# SCH_sonnn_2025-09-09.net
KiCad netlist of a schematic drawn in EasyEDA
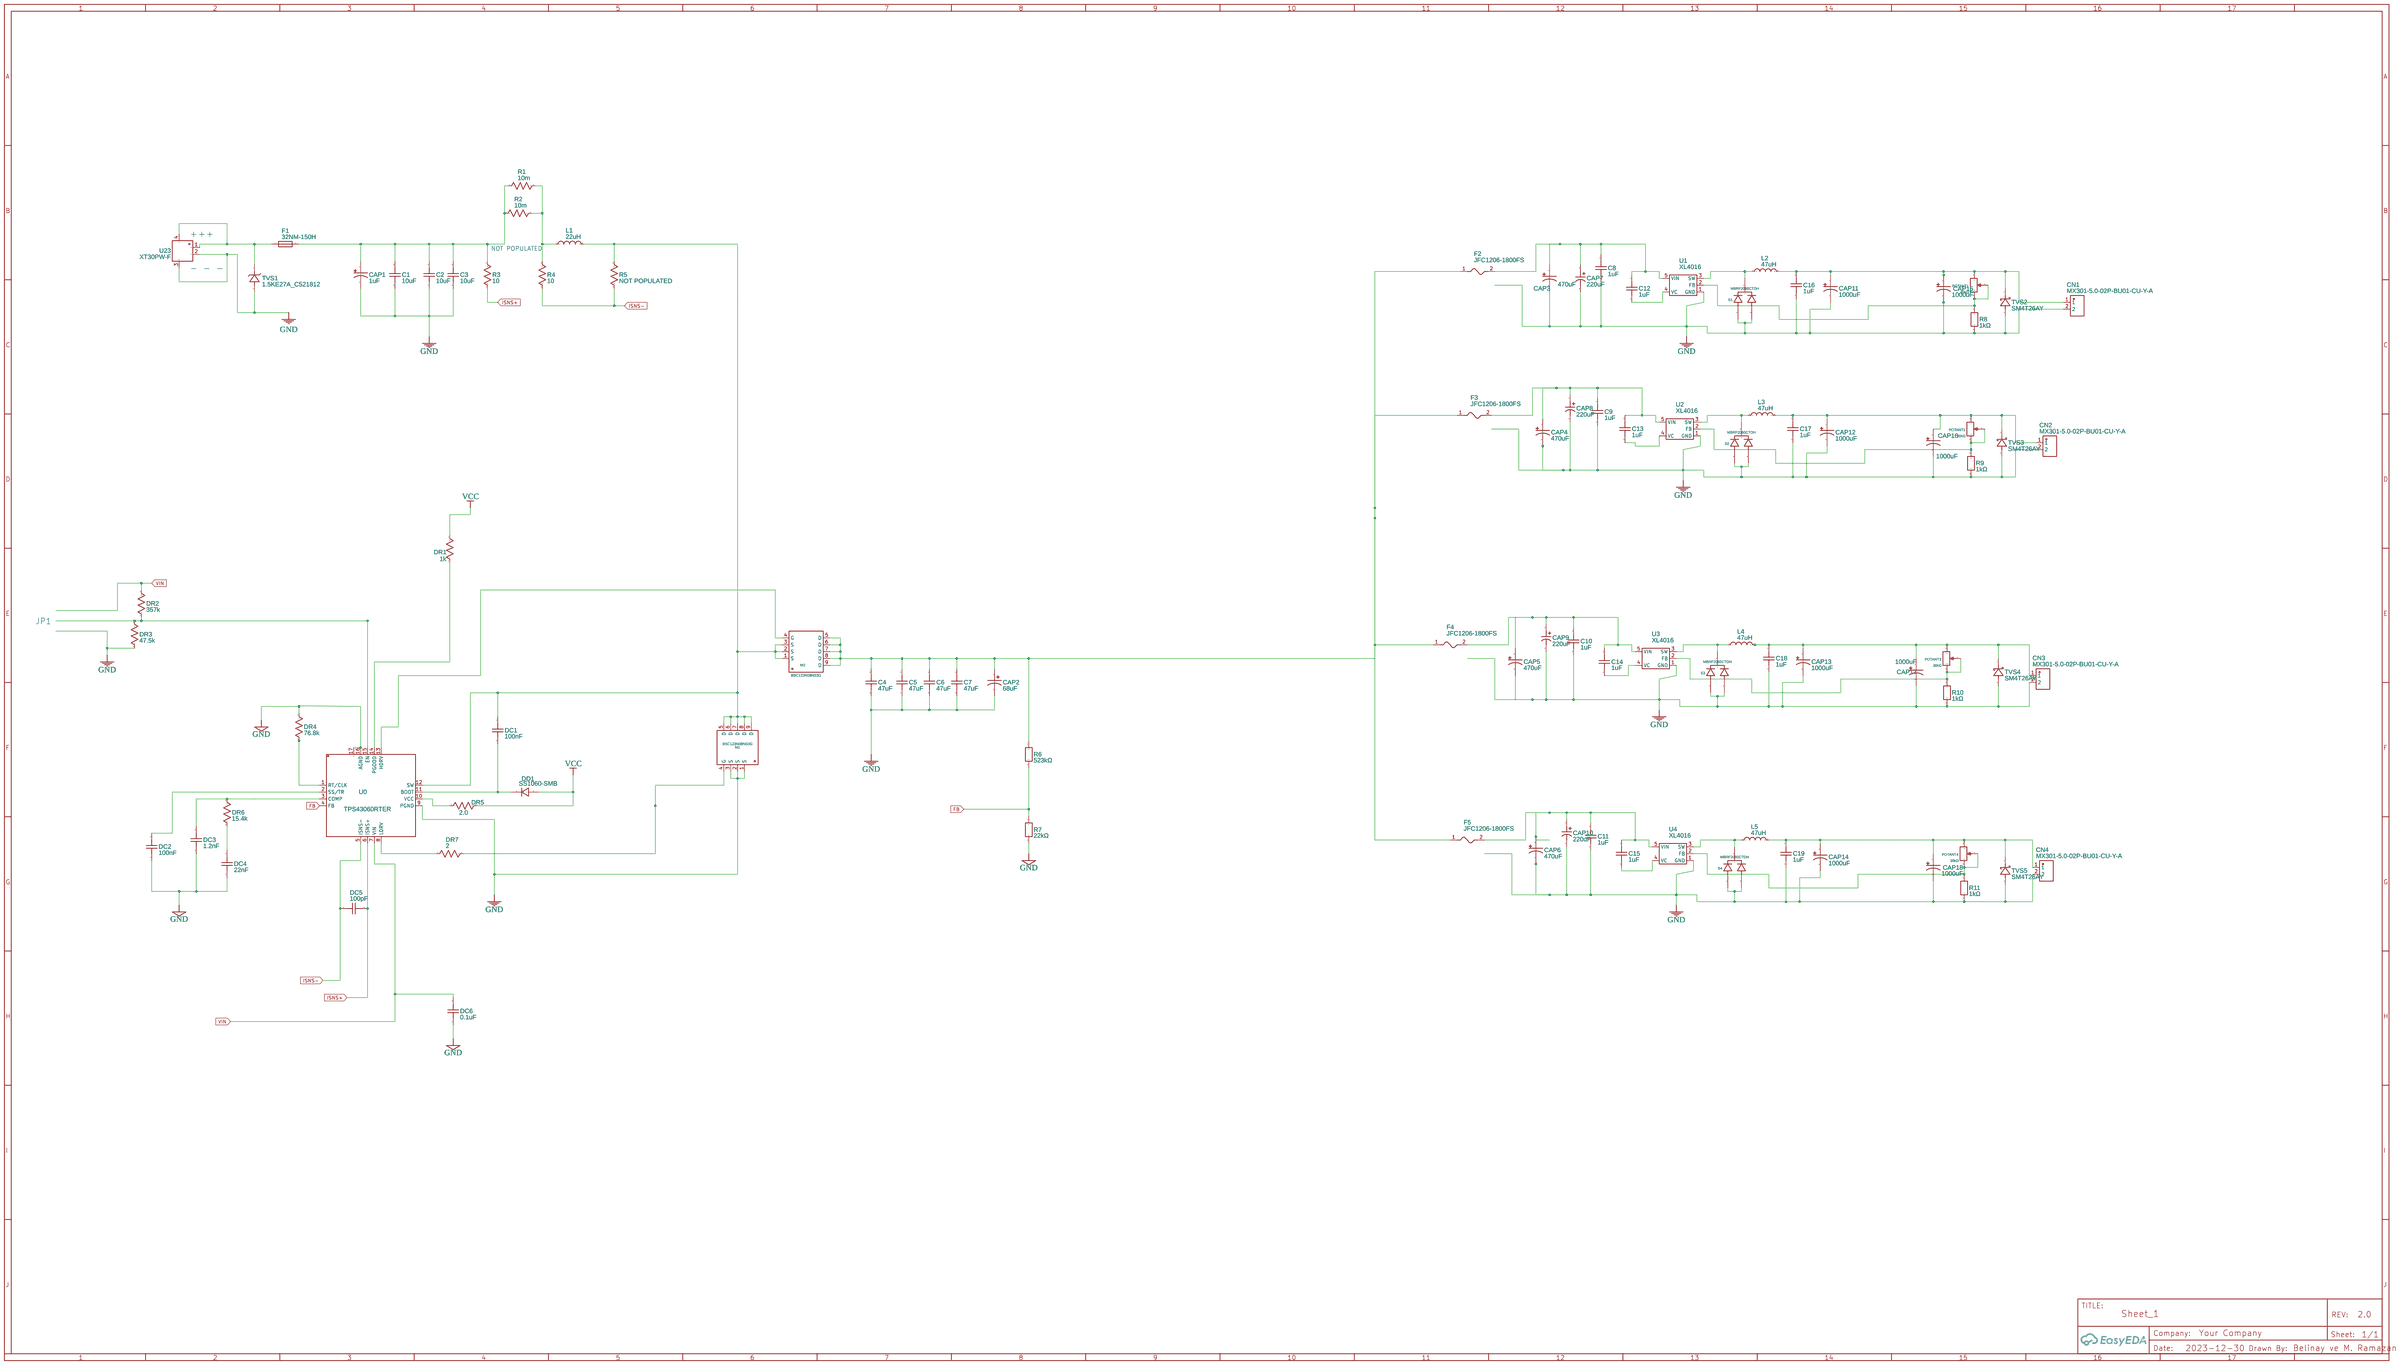
[diagram p0: schematic sheet]

(export (version "E")
  (design (tool "Eeschema 10.0.6"))
  (components
    (comp (ref "C1")
      (value "10uF")
      (fields (field (name "Manufacturer Part") "CNC6P1X7R1H106K250AE") (field (name "Manufacturer") "TDK"))
      (libsource (lib "") (part "CNC6P1X7R1H106K250AE"))
    )
    (comp (ref "C2")
      (value "10uF")
      (fields (field (name "Manufacturer Part") "CNC6P1X7R1H106K250AE") (field (name "Manufacturer") "TDK"))
      (libsource (lib "") (part "CNC6P1X7R1H106K250AE"))
    )
    (comp (ref "C3")
      (value "10uF")
      (fields (field (name "Manufacturer Part") "CNC6P1X7R1H106K250AE") (field (name "Manufacturer") "TDK"))
      (libsource (lib "") (part "CNC6P1X7R1H106K250AE"))
    )
    (comp (ref "C4") (value "47uF") (libsource (lib "") (part "C_0603_US")))
    (comp (ref "C5") (value "47uF") (libsource (lib "") (part "C_0603_US")))
    (comp (ref "C6") (value "47uF") (libsource (lib "") (part "C_0603_US")))
    (comp (ref "C7") (value "47uF") (libsource (lib "") (part "C_0603_US")))
    (comp (ref "C8")
      (value "1uF")
      (fields (field (name "Manufacturer Part") "FK26X7R1H105KRE06") (field (name "Manufacturer") "TDK"))
      (libsource (lib "") (part "FK26X7R1H105KRE06"))
    )
    (comp (ref "C9")
      (value "1uF")
      (fields (field (name "Manufacturer Part") "FK26X7R1H105KRE06") (field (name "Manufacturer") "TDK"))
      (libsource (lib "") (part "FK26X7R1H105KRE06"))
    )
    (comp (ref "C10")
      (value "1uF")
      (fields (field (name "Manufacturer Part") "FK26X7R1H105KRE06") (field (name "Manufacturer") "TDK"))
      (libsource (lib "") (part "FK26X7R1H105KRE06"))
    )
    (comp (ref "C11")
      (value "1uF")
      (fields (field (name "Manufacturer Part") "FK26X7R1H105KRE06") (field (name "Manufacturer") "TDK"))
      (libsource (lib "") (part "FK26X7R1H105KRE06"))
    )
    (comp (ref "C12")
      (value "1uF")
      (fields (field (name "Manufacturer Part") "C1005X6S1A105K050BC") (field (name "Manufacturer") "TDK"))
      (libsource (lib "") (part "C1005X6S1A105K050BC"))
    )
    (comp (ref "C13")
      (value "1uF")
      (fields (field (name "Manufacturer Part") "C1005X6S1A105K050BC") (field (name "Manufacturer") "TDK"))
      (libsource (lib "") (part "C1005X6S1A105K050BC"))
    )
    (comp (ref "C14")
      (value "1uF")
      (fields (field (name "Manufacturer Part") "C1005X6S1A105K050BC") (field (name "Manufacturer") "TDK"))
      (libsource (lib "") (part "C1005X6S1A105K050BC"))
    )
    (comp (ref "C15")
      (value "1uF")
      (fields (field (name "Manufacturer Part") "C1005X6S1A105K050BC") (field (name "Manufacturer") "TDK"))
      (libsource (lib "") (part "C1005X6S1A105K050BC_1"))
    )
    (comp (ref "C16")
      (value "1uF")
      (fields (field (name "Manufacturer Part") "FK26X7R1H105KRE06") (field (name "Manufacturer") "TDK"))
      (libsource (lib "") (part "FK26X7R1H105KRE06"))
    )
    (comp (ref "C17")
      (value "1uF")
      (fields (field (name "Manufacturer Part") "FK26X7R1H105KRE06") (field (name "Manufacturer") "TDK"))
      (libsource (lib "") (part "FK26X7R1H105KRE06_1"))
    )
    (comp (ref "C18")
      (value "1uF")
      (fields (field (name "Manufacturer Part") "FK26X7R1H105KRE06") (field (name "Manufacturer") "TDK"))
      (libsource (lib "") (part "FK26X7R1H105KRE06"))
    )
    (comp (ref "C19")
      (value "1uF")
      (fields (field (name "Manufacturer Part") "FK26X7R1H105KRE06") (field (name "Manufacturer") "TDK"))
      (libsource (lib "") (part "FK26X7R1H105KRE06"))
    )
    (comp (ref "CAP1")
      (value "1uF")
      (fields (field (name "Manufacturer Part") "HT2A1R0M0405") (field (name "Manufacturer") "HONOR(荣誉)"))
      (libsource (lib "") (part "RVT2A1R0M0405"))
    )
    (comp (ref "CAP2") (value "68uF") (libsource (lib "") (part "C_Tan_SMD_A_US")))
    (comp (ref "CAP3")
      (value "470uF")
      (fields
        (field (name "Manufacturer Part") "RC063M471LO13*20TH-2A1E")
        (field (name "Manufacturer") "BERYL(绿宝石)")
      )
      (libsource (lib "") (part "RC063M471LO13*20TH-2A1E_1"))
    )
    (comp (ref "CAP4")
      (value "470uF")
      (fields
        (field (name "Manufacturer Part") "RC063M471LO13*20TH-2A1E")
        (field (name "Manufacturer") "BERYL(绿宝石)")
      )
      (libsource (lib "") (part "RC063M471LO13*20TH-2A1E_1"))
    )
    (comp (ref "CAP5")
      (value "470uF")
      (fields
        (field (name "Manufacturer Part") "RC063M471LO13*20TH-2A1E")
        (field (name "Manufacturer") "BERYL(绿宝石)")
      )
      (libsource (lib "") (part "RC063M471LO13*20TH-2A1E_1"))
    )
    (comp (ref "CAP6")
      (value "470uF")
      (fields
        (field (name "Manufacturer Part") "RC063M471LO13*20TH-2A1E")
        (field (name "Manufacturer") "BERYL(绿宝石)")
      )
      (libsource (lib "") (part "RC063M471LO13*20TH-2A1E"))
    )
    (comp (ref "CAP7")
      (value "220uF")
      (fields (field (name "Manufacturer Part") "189RV0038") (field (name "Manufacturer") "KNSCHA(科尼盛)"))
      (libsource (lib "") (part "189RV0038"))
    )
    (comp (ref "CAP8")
      (value "220uF")
      (fields (field (name "Manufacturer Part") "189RV0038") (field (name "Manufacturer") "KNSCHA(科尼盛)"))
      (libsource (lib "") (part "189RV0038"))
    )
    (comp (ref "CAP9")
      (value "220uF")
      (fields (field (name "Manufacturer Part") "189RV0038") (field (name "Manufacturer") "KNSCHA(科尼盛)"))
      (libsource (lib "") (part "189RV0038"))
    )
    (comp (ref "CAP10")
      (value "220uF")
      (fields (field (name "Manufacturer Part") "189RV0038") (field (name "Manufacturer") "KNSCHA(科尼盛)"))
      (libsource (lib "") (part "189RV0038"))
    )
    (comp (ref "CAP11")
      (value "1000uF")
      (fields (field (name "Manufacturer Part") "PKCL2001H102MF") (field (name "Manufacturer") "Ymin(永铭)"))
      (libsource (lib "") (part "PKCL21H102MF"))
    )
    (comp (ref "CAP12")
      (value "1000uF")
      (fields (field (name "Manufacturer Part") "PKCL2001H102MF") (field (name "Manufacturer") "Ymin(永铭)"))
      (libsource (lib "") (part "PKCL21H102MF"))
    )
    (comp (ref "CAP13")
      (value "1000uF")
      (fields (field (name "Manufacturer Part") "PKCL2001H102MF") (field (name "Manufacturer") "Ymin(永铭)"))
      (libsource (lib "") (part "PKCL21H102MF"))
    )
    (comp (ref "CAP14")
      (value "1000uF")
      (fields (field (name "Manufacturer Part") "PKCL2001H102MF") (field (name "Manufacturer") "Ymin(永铭)"))
      (libsource (lib "") (part "PKCL21H102MF_1"))
    )
    (comp (ref "CAP15")
      (value "1000uF")
      (fields (field (name "Manufacturer Part") "LKML3001J102MF") (field (name "Manufacturer") "Ymin(永铭)"))
      (libsource (lib "") (part "LKML3001J102MF_1"))
    )
    (comp (ref "CAP16")
      (value "1000uF")
      (fields (field (name "Manufacturer Part") "LKML3001J102MF") (field (name "Manufacturer") "Ymin(永铭)"))
      (libsource (lib "") (part "LKML3001J102MF_1"))
    )
    (comp (ref "CAP17")
      (value "1000uF")
      (fields (field (name "Manufacturer Part") "LKML3001J102MF") (field (name "Manufacturer") "Ymin(永铭)"))
      (libsource (lib "") (part "LKML3001J102MF"))
    )
    (comp (ref "CAP18")
      (value "1000uF")
      (fields (field (name "Manufacturer Part") "LKML3001J102MF") (field (name "Manufacturer") "Ymin(永铭)"))
      (libsource (lib "") (part "LKML3001J102MF"))
    )
    (comp (ref "CN1")
      (value "MX301-5.0-02P-BU01-CU-Y-A")
      (fields
        (field (name "Manufacturer Part") "MX301-5.0-02P-BU01-Cu-Y-A")
        (field (name "Manufacturer") "MAX(迈旭)")
      )
      (libsource (lib "") (part "MX301-5.0-02P-BU01-CU-Y-A"))
    )
    (comp (ref "CN2")
      (value "MX301-5.0-02P-BU01-CU-Y-A")
      (fields
        (field (name "Manufacturer Part") "MX301-5.0-02P-BU01-Cu-Y-A")
        (field (name "Manufacturer") "MAX(迈旭)")
      )
      (libsource (lib "") (part "MX301-5.0-02P-BU01-CU-Y-A"))
    )
    (comp (ref "CN3")
      (value "MX301-5.0-02P-BU01-CU-Y-A")
      (fields
        (field (name "Manufacturer Part") "MX301-5.0-02P-BU01-Cu-Y-A")
        (field (name "Manufacturer") "MAX(迈旭)")
      )
      (libsource (lib "") (part "MX301-5.0-02P-BU01-CU-Y-A"))
    )
    (comp (ref "CN4")
      (value "MX301-5.0-02P-BU01-CU-Y-A")
      (fields
        (field (name "Manufacturer Part") "MX301-5.0-02P-BU01-Cu-Y-A")
        (field (name "Manufacturer") "MAX(迈旭)")
      )
      (libsource (lib "") (part "MX301-5.0-02P-BU01-CU-Y-A"))
    )
    (comp (ref "DC1")
      (value "100nF")
      (fields
        (field (name "Manufacturer Part") "DCS104M26Y5UH6FJ5A0")
        (field (name "Manufacturer") "SHM(南方宏明)")
      )
      (libsource (lib "") (part "DCS104M26Y5UH6FJ5A0"))
    )
    (comp (ref "DC2")
      (value "100nF")
      (fields
        (field (name "Manufacturer Part") "DCS104M26Y5UH6FJ5A0")
        (field (name "Manufacturer") "SHM(南方宏明)")
      )
      (libsource (lib "") (part "DCS104M26Y5UH6FJ5A0_1"))
    )
    (comp (ref "DC3")
      (value "1.2nF")
      (fields (field (name "Manufacturer Part") "PE122J2A0501") (field (name "Manufacturer") "KYET(科雅)"))
      (libsource (lib "") (part "PE122J2A0501"))
    )
    (comp (ref "DC4")
      (value "22nF")
      (fields
        (field (name "Manufacturer Part") "DCM223M39Y5VL6FJ5A0")
        (field (name "Manufacturer") "SHM(南方宏明)")
      )
      (libsource (lib "") (part "DCM223M39Y5VL6FJ5A0"))
    )
    (comp (ref "DC5")
      (value "100pF")
      (fields
        (field (name "Manufacturer Part") "DCC101J26COHF6FJ5A0")
        (field (name "Manufacturer") "SHM(南方宏明)")
      )
      (libsource (lib "") (part "DCC101J26COHF6FJ5A0"))
    )
    (comp (ref "DC6") (value "0.1uF") (libsource (lib "") (part "C_0603_US_1")))
    (comp (ref "DD1")
      (value "SS1060-SMB")
      (fields (field (name "Manufacturer") "GOODWORK(固得沃克)"))
      (libsource (lib "") (part "SS1060-SMB"))
    )
    (comp (ref "DR1") (value "1k") (libsource (lib "") (part "R_AXIAL-0.3_US_1")))
    (comp (ref "DR2") (value "357k") (libsource (lib "") (part "R_AXIAL-0.3_US_1")))
    (comp (ref "DR3") (value "47.5k") (libsource (lib "") (part "R_AXIAL-0.3_US_1")))
    (comp (ref "DR4") (value "76.8k") (libsource (lib "") (part "R_AXIAL-0.3_US_1")))
    (comp (ref "DR5") (value "2.0") (libsource (lib "") (part "R_AXIAL-0.3_US")))
    (comp (ref "DR6") (value "15.4k") (libsource (lib "") (part "R_AXIAL-0.3_US_1")))
    (comp (ref "DR7") (value "2") (libsource (lib "") (part "R_0603_US")))
    (comp (ref "F1")
      (value "32NM-150H")
      (fields (field (name "Manufacturer") "HOLLY(好利来)"))
      (libsource (lib "") (part "32NM-150H"))
    )
    (comp (ref "F2")
      (value "JFC1206-1800FS")
      (fields (field (name "Manufacturer") "JDTfuse(集电通)"))
      (libsource (lib "") (part "JFC1206-1800FS"))
    )
    (comp (ref "F3")
      (value "JFC1206-1800FS")
      (fields (field (name "Manufacturer") "JDTfuse(集电通)"))
      (libsource (lib "") (part "JFC1206-1800FS"))
    )
    (comp (ref "F4")
      (value "JFC1206-1800FS")
      (fields (field (name "Manufacturer") "JDTfuse(集电通)"))
      (libsource (lib "") (part "JFC1206-1800FS"))
    )
    (comp (ref "F5")
      (value "JFC1206-1800FS")
      (fields (field (name "Manufacturer") "JDTfuse(集电通)"))
      (libsource (lib "") (part "JFC1206-1800FS"))
    )
    (comp (ref "L1")
      (value "22uH")
      (fields
        (field (name "Manufacturer Part") "PDMTAT068125-220MLU")
        (field (name "Manufacturer") "PROD(谱罗德)")
      )
      (libsource (lib "") (part "PDMTAT068125-220MLU"))
    )
    (comp (ref "L2")
      (value "47uH")
      (fields (field (name "Manufacturer Part") "PDPMAA1712-470MP") (field (name "Manufacturer") "PROD(谱罗德)"))
      (libsource (lib "") (part "PDPMAA1712-470MP"))
    )
    (comp (ref "L3")
      (value "47uH")
      (fields (field (name "Manufacturer Part") "PDPMAA1712-470MP") (field (name "Manufacturer") "PROD(谱罗德)"))
      (libsource (lib "") (part "PDPMAA1712-470MP"))
    )
    (comp (ref "L4")
      (value "47uH")
      (fields (field (name "Manufacturer Part") "PDPMAA1712-470MP") (field (name "Manufacturer") "PROD(谱罗德)"))
      (libsource (lib "") (part "PDPMAA1712-470MP"))
    )
    (comp (ref "L5")
      (value "47uH")
      (fields (field (name "Manufacturer Part") "PDPMAA1712-470MP") (field (name "Manufacturer") "PROD(谱罗德)"))
      (libsource (lib "") (part "PDPMAA1712-470MP"))
    )
    (comp (ref "M1")
      (value "BSC123N08NS3G")
      (fields (field (name "Manufacturer") "Infineon(英飞凌)"))
      (libsource (lib "") (part "BSC123N08NS3G_1"))
    )
    (comp (ref "M2")
      (value "BSC123N08NS3G")
      (fields (field (name "Manufacturer") "Infineon(英飞凌)"))
      (libsource (lib "") (part "BSC123N08NS3G"))
    )
    (comp (ref "POTANT1")
      (value "30kΩ")
      (fields (field (name "Manufacturer Part") "3362P-1-103LF") (field (name "Manufacturer") "BOURNS"))
      (libsource (lib "") (part "3362P-1-103LF"))
    )
    (comp (ref "POTANT2")
      (value "30kΩ")
      (fields (field (name "Manufacturer Part") "3362P-1-103LF") (field (name "Manufacturer") "BOURNS"))
      (libsource (lib "") (part "3362P-1-103LF"))
    )
    (comp (ref "POTANT3")
      (value "30kΩ")
      (fields (field (name "Manufacturer Part") "3362P-1-103LF") (field (name "Manufacturer") "BOURNS"))
      (libsource (lib "") (part "3362P-1-103LF"))
    )
    (comp (ref "POTANT4")
      (value "30kΩ")
      (fields (field (name "Manufacturer Part") "3362P-1-103LF") (field (name "Manufacturer") "BOURNS"))
      (libsource (lib "") (part "3362P-1-103LF"))
    )
    (comp (ref "R1") (value "10m") (libsource (lib "") (part "R_AXIAL-0.3_US_2")))
    (comp (ref "R2") (value "10m") (libsource (lib "") (part "R_AXIAL-0.3_US_2")))
    (comp (ref "R3") (value "10") (libsource (lib "") (part "R_AXIAL-0.3_US_3")))
    (comp (ref "R4") (value "10") (libsource (lib "") (part "R_AXIAL-0.3_US_3")))
    (comp (ref "R5") (value "NOT POPULATED") (libsource (lib "") (part "R_AXIAL-0.3_US_3")))
    (comp (ref "R6")
      (value "523kΩ")
      (fields (field (name "Manufacturer Part") "MFR-25FBF52-523K") (field (name "Manufacturer") "YAGEO(国巨)"))
      (libsource (lib "") (part "MFR-25FBF52-523K"))
    )
    (comp (ref "R7")
      (value "22kΩ")
      (fields
        (field (name "Manufacturer Part") "RN 3WS 22K F T/B A1")
        (field (name "Manufacturer") "Tyohm(幸亚电阻)")
      )
      (libsource (lib "") (part "RN 3WS 22K F T/B A1"))
    )
    (comp (ref "R8")
      (value "1kΩ")
      (fields (field (name "Manufacturer Part") "MF0207FTE52-1K") (field (name "Manufacturer") "YAGEO(国巨)"))
      (libsource (lib "") (part "MF0207FTE52-1K"))
    )
    (comp (ref "R9")
      (value "1kΩ")
      (fields (field (name "Manufacturer Part") "MF0207FTE52-1K") (field (name "Manufacturer") "YAGEO(国巨)"))
      (libsource (lib "") (part "MF0207FTE52-1K"))
    )
    (comp (ref "R10")
      (value "1kΩ")
      (fields (field (name "Manufacturer Part") "MF0207FTE52-1K") (field (name "Manufacturer") "YAGEO(国巨)"))
      (libsource (lib "") (part "MF0207FTE52-1K"))
    )
    (comp (ref "R11")
      (value "1kΩ")
      (fields (field (name "Manufacturer Part") "MF0207FTE52-1K") (field (name "Manufacturer") "YAGEO(国巨)"))
      (libsource (lib "") (part "MF0207FTE52-1K"))
    )
    (comp (ref "S1")
      (value "MBRF2060CTDH")
      (fields (field (name "Manufacturer") "迪一"))
      (libsource (lib "") (part "MBRF2060CTDH"))
    )
    (comp (ref "S2")
      (value "MBRF2060CTDH")
      (fields (field (name "Manufacturer") "迪一"))
      (libsource (lib "") (part "MBRF2060CTDH"))
    )
    (comp (ref "S3")
      (value "MBRF2060CTDH")
      (fields (field (name "Manufacturer") "迪一"))
      (libsource (lib "") (part "MBRF2060CTDH"))
    )
    (comp (ref "S4")
      (value "MBRF2060CTDH")
      (fields (field (name "Manufacturer") "迪一"))
      (libsource (lib "") (part "MBRF2060CTDH"))
    )
    (comp (ref "TVS1")
      (value "1.5KE27A_C521812")
      (fields
        (field (name "Manufacturer Part") "1.5KE27A/B")
        (field (name "Manufacturer") "Brightking(君耀电子)")
      )
      (libsource (lib "") (part "1.5KE27A_C521812"))
    )
    (comp (ref "TVS2")
      (value "SM4T26AY")
      (fields (field (name "Manufacturer") "ST(意法半导体)"))
      (libsource (lib "") (part "SM4T26AY"))
    )
    (comp (ref "TVS3")
      (value "SM4T26AY")
      (fields (field (name "Manufacturer") "ST(意法半导体)"))
      (libsource (lib "") (part "SM4T26AY"))
    )
    (comp (ref "TVS4")
      (value "SM4T26AY")
      (fields (field (name "Manufacturer") "ST(意法半导体)"))
      (libsource (lib "") (part "SM4T26AY"))
    )
    (comp (ref "TVS5")
      (value "SM4T26AY")
      (fields (field (name "Manufacturer") "ST(意法半导体)"))
      (libsource (lib "") (part "SM4T26AY"))
    )
    (comp (ref "U0")
      (value "TPS43060RTER")
      (fields (field (name "Manufacturer") "TI(德州仪器)"))
      (libsource (lib "") (part "TPS43060RTER"))
    )
    (comp (ref "U1")
      (value "XL4016")
      (fields (field (name "Manufacturer Part") "XL4016E1") (field (name "Manufacturer") "XLSEMI"))
      (libsource (lib "") (part "XL4016"))
    )
    (comp (ref "U2")
      (value "XL4016")
      (fields (field (name "Manufacturer Part") "XL4016E1") (field (name "Manufacturer") "XLSEMI"))
      (libsource (lib "") (part "XL4016"))
    )
    (comp (ref "U3")
      (value "XL4016")
      (fields (field (name "Manufacturer Part") "XL4016E1") (field (name "Manufacturer") "XLSEMI"))
      (libsource (lib "") (part "XL4016"))
    )
    (comp (ref "U4")
      (value "XL4016")
      (fields (field (name "Manufacturer Part") "XL4016E1") (field (name "Manufacturer") "XLSEMI"))
      (libsource (lib "") (part "XL4016"))
    )
    (comp (ref "U23") (value "XT30PW-F") (libsource (lib "") (part "XT30PW-F")))
  )
  (nets
    (net (code "1") (name "FB") (class "Default")
      (node (ref "R6") (pin "1") (pinfunction "1_1") (pintype "unspecified"))
      (node (ref "R7") (pin "1") (pinfunction "1_1") (pintype "unspecified"))
      (node (ref "U0") (pin "4") (pinfunction "FB_4") (pintype "unspecified"))
    )
    (net (code "2") (name "GND") (class "Default")
      (node (ref "C1") (pin "1") (pinfunction "1_1") (pintype "unspecified"))
      (node (ref "C10") (pin "2") (pinfunction "2_2") (pintype "unspecified"))
      (node (ref "C11") (pin "2") (pinfunction "2_2") (pintype "unspecified"))
      (node (ref "C16") (pin "2") (pinfunction "2_2") (pintype "unspecified"))
      (node (ref "C17") (pin "1") (pinfunction "1_1") (pintype "unspecified"))
      (node (ref "C18") (pin "2") (pinfunction "2_2") (pintype "unspecified"))
      (node (ref "C19") (pin "2") (pinfunction "2_2") (pintype "unspecified"))
      (node (ref "C2") (pin "1") (pinfunction "1_1") (pintype "unspecified"))
      (node (ref "C3") (pin "1") (pinfunction "1_1") (pintype "unspecified"))
      (node (ref "C4") (pin "1") (pinfunction "1_1") (pintype "unspecified"))
      (node (ref "C5") (pin "1") (pinfunction "1_1") (pintype "unspecified"))
      (node (ref "C6") (pin "1") (pinfunction "1_1") (pintype "unspecified"))
      (node (ref "C7") (pin "1") (pinfunction "1_1") (pintype "unspecified"))
      (node (ref "C8") (pin "2") (pinfunction "2_2") (pintype "unspecified"))
      (node (ref "C9") (pin "2") (pinfunction "2_2") (pintype "unspecified"))
      (node (ref "CAP1") (pin "2") (pinfunction "2_2") (pintype "unspecified"))
      (node (ref "CAP10") (pin "2") (pinfunction "2_2") (pintype "input"))
      (node (ref "CAP11") (pin "2") (pinfunction "2_2") (pintype "unspecified"))
      (node (ref "CAP12") (pin "2") (pinfunction "2_2") (pintype "unspecified"))
      (node (ref "CAP13") (pin "2") (pinfunction "2_2") (pintype "unspecified"))
      (node (ref "CAP14") (pin "2") (pinfunction "2_2") (pintype "unspecified"))
      (node (ref "CAP15") (pin "2") (pinfunction "2_2") (pintype "unspecified"))
      (node (ref "CAP16") (pin "2") (pinfunction "2_2") (pintype "unspecified"))
      (node (ref "CAP17") (pin "2") (pinfunction "2_2") (pintype "unspecified"))
      (node (ref "CAP18") (pin "2") (pinfunction "2_2") (pintype "unspecified"))
      (node (ref "CAP2") (pin "2") (pinfunction "2_2") (pintype "unspecified"))
      (node (ref "CAP3") (pin "2") (pinfunction "2_2") (pintype "unspecified"))
      (node (ref "CAP4") (pin "2") (pinfunction "2_2") (pintype "unspecified"))
      (node (ref "CAP5") (pin "2") (pinfunction "2_2") (pintype "unspecified"))
      (node (ref "CAP6") (pin "2") (pinfunction "2_2") (pintype "unspecified"))
      (node (ref "CAP7") (pin "2") (pinfunction "2_2") (pintype "input"))
      (node (ref "CAP8") (pin "2") (pinfunction "2_2") (pintype "input"))
      (node (ref "CAP9") (pin "2") (pinfunction "2_2") (pintype "input"))
      (node (ref "CN1") (pin "2") (pinfunction "2_2") (pintype "unspecified"))
      (node (ref "CN2") (pin "2") (pinfunction "2_2") (pintype "unspecified"))
      (node (ref "CN3") (pin "2") (pinfunction "2_2") (pintype "unspecified"))
      (node (ref "CN4") (pin "2") (pinfunction "2_2") (pintype "unspecified"))
      (node (ref "DC2") (pin "1") (pinfunction "1_1") (pintype "unspecified"))
      (node (ref "DC3") (pin "1") (pinfunction "1_1") (pintype "unspecified"))
      (node (ref "DC4") (pin "1") (pinfunction "1_1") (pintype "unspecified"))
      (node (ref "DC6") (pin "1") (pinfunction "1_1") (pintype "unspecified"))
      (node (ref "DR3") (pin "1") (pinfunction "1_1") (pintype "unspecified"))
      (node (ref "DR4") (pin "2") (pinfunction "2_2") (pintype "unspecified"))
      (node (ref "M1") (pin "1") (pinfunction "S_1") (pintype "unspecified"))
      (node (ref "M1") (pin "2") (pinfunction "S_2") (pintype "unspecified"))
      (node (ref "M1") (pin "3") (pinfunction "S_3") (pintype "unspecified"))
      (node (ref "R10") (pin "2") (pinfunction "2_2") (pintype "unspecified"))
      (node (ref "R11") (pin "2") (pinfunction "2_2") (pintype "unspecified"))
      (node (ref "R7") (pin "2") (pinfunction "2_2") (pintype "unspecified"))
      (node (ref "R8") (pin "2") (pinfunction "2_2") (pintype "unspecified"))
      (node (ref "R9") (pin "2") (pinfunction "2_2") (pintype "unspecified"))
      (node (ref "S1") (pin "1") (pinfunction "1_1") (pintype "unspecified"))
      (node (ref "S1") (pin "3") (pinfunction "3_3") (pintype "unspecified"))
      (node (ref "S2") (pin "1") (pinfunction "1_1") (pintype "unspecified"))
      (node (ref "S2") (pin "3") (pinfunction "3_3") (pintype "unspecified"))
      (node (ref "S3") (pin "1") (pinfunction "1_1") (pintype "unspecified"))
      (node (ref "S3") (pin "3") (pinfunction "3_3") (pintype "unspecified"))
      (node (ref "S4") (pin "1") (pinfunction "1_1") (pintype "unspecified"))
      (node (ref "S4") (pin "3") (pinfunction "3_3") (pintype "unspecified"))
      (node (ref "TVS1") (pin "2") (pinfunction "A_2") (pintype "unspecified"))
      (node (ref "TVS2") (pin "2") (pinfunction "2_2") (pintype "unspecified"))
      (node (ref "TVS3") (pin "2") (pinfunction "2_2") (pintype "unspecified"))
      (node (ref "TVS4") (pin "2") (pinfunction "2_2") (pintype "unspecified"))
      (node (ref "TVS5") (pin "2") (pinfunction "2_2") (pintype "unspecified"))
      (node (ref "U0") (pin "16") (pinfunction "AGND_16") (pintype "unspecified"))
      (node (ref "U0") (pin "17") (pinfunction "PAD_17") (pintype "unspecified"))
      (node (ref "U0") (pin "9") (pinfunction "PGND_9") (pintype "unspecified"))
      (node (ref "U1") (pin "1") (pinfunction "GND_1") (pintype "unspecified"))
      (node (ref "U2") (pin "1") (pinfunction "GND_1") (pintype "unspecified"))
      (node (ref "U23") (pin "2") (pinfunction "2_2") (pintype "unspecified"))
      (node (ref "U23") (pin "3") (pinfunction "3_3") (pintype "unspecified"))
      (node (ref "U3") (pin "1") (pinfunction "GND_1") (pintype "unspecified"))
      (node (ref "U4") (pin "1") (pinfunction "GND_1") (pintype "unspecified"))
    )
    (net (code "3") (name "ISNS+") (class "Default")
      (node (ref "DC5") (pin "2") (pinfunction "2_2") (pintype "unspecified"))
      (node (ref "R3") (pin "1") (pinfunction "1_1") (pintype "unspecified"))
      (node (ref "U0") (pin "6") (pinfunction "ISNS+_6") (pintype "unspecified"))
    )
    (net (code "4") (name "ISNS-") (class "Default")
      (node (ref "DC5") (pin "1") (pinfunction "1_1") (pintype "unspecified"))
      (node (ref "R4") (pin "1") (pinfunction "1_1") (pintype "unspecified"))
      (node (ref "R5") (pin "1") (pinfunction "1_1") (pintype "unspecified"))
      (node (ref "U0") (pin "5") (pinfunction "ISNS-_5") (pintype "unspecified"))
    )
    (net (code "5") (name "Net-(C1-Pad2)") (class "Default")
      (node (ref "C1") (pin "2") (pinfunction "2_2") (pintype "unspecified"))
      (node (ref "C2") (pin "2") (pinfunction "2_2") (pintype "unspecified"))
      (node (ref "C3") (pin "2") (pinfunction "2_2") (pintype "unspecified"))
      (node (ref "CAP1") (pin "1") (pinfunction "1_1") (pintype "unspecified"))
      (node (ref "F1") (pin "2") (pinfunction "2_2") (pintype "unspecified"))
      (node (ref "R1") (pin "1") (pinfunction "1_1") (pintype "unspecified"))
      (node (ref "R2") (pin "1") (pinfunction "1_1") (pintype "unspecified"))
      (node (ref "R3") (pin "2") (pinfunction "2_2") (pintype "unspecified"))
    )
    (net (code "6") (name "Net-(C4-Pad2)") (class "Default")
      (node (ref "C4") (pin "2") (pinfunction "2_2") (pintype "unspecified"))
      (node (ref "C5") (pin "2") (pinfunction "2_2") (pintype "unspecified"))
      (node (ref "C6") (pin "2") (pinfunction "2_2") (pintype "unspecified"))
      (node (ref "C7") (pin "2") (pinfunction "2_2") (pintype "unspecified"))
      (node (ref "CAP2") (pin "1") (pinfunction "1_1") (pintype "unspecified"))
      (node (ref "F2") (pin "1") (pinfunction "1_1") (pintype "unspecified"))
      (node (ref "F3") (pin "1") (pinfunction "1_1") (pintype "unspecified"))
      (node (ref "F4") (pin "1") (pinfunction "1_1") (pintype "unspecified"))
      (node (ref "F5") (pin "1") (pinfunction "1_1") (pintype "unspecified"))
      (node (ref "M2") (pin "5") (pinfunction "D_5") (pintype "unspecified"))
      (node (ref "M2") (pin "6") (pinfunction "D_6") (pintype "unspecified"))
      (node (ref "M2") (pin "7") (pinfunction "D_7") (pintype "unspecified"))
      (node (ref "M2") (pin "8") (pinfunction "D_8") (pintype "unspecified"))
      (node (ref "M2") (pin "9") (pinfunction "D_9") (pintype "unspecified"))
      (node (ref "R6") (pin "2") (pinfunction "2_2") (pintype "unspecified"))
    )
    (net (code "7") (name "Net-(C16-Pad1)") (class "Default")
      (node (ref "C16") (pin "1") (pinfunction "1_1") (pintype "unspecified"))
      (node (ref "CAP11") (pin "1") (pinfunction "1_1") (pintype "unspecified"))
      (node (ref "CAP15") (pin "1") (pinfunction "1_1") (pintype "unspecified"))
      (node (ref "CN1") (pin "1") (pinfunction "1_1") (pintype "unspecified"))
      (node (ref "L2") (pin "2") (pinfunction "2_2") (pintype "unspecified"))
      (node (ref "POTANT1") (pin "1") (pinfunction "1_1") (pintype "input"))
      (node (ref "TVS2") (pin "1") (pinfunction "1_1") (pintype "unspecified"))
    )
    (net (code "8") (name "Net-(C17-Pad2)") (class "Default")
      (node (ref "C17") (pin "2") (pinfunction "2_2") (pintype "unspecified"))
      (node (ref "CAP12") (pin "1") (pinfunction "1_1") (pintype "unspecified"))
      (node (ref "CAP16") (pin "1") (pinfunction "1_1") (pintype "unspecified"))
      (node (ref "CN2") (pin "1") (pinfunction "1_1") (pintype "unspecified"))
      (node (ref "L3") (pin "2") (pinfunction "2_2") (pintype "unspecified"))
      (node (ref "POTANT2") (pin "1") (pinfunction "1_1") (pintype "input"))
      (node (ref "TVS3") (pin "1") (pinfunction "1_1") (pintype "unspecified"))
    )
    (net (code "9") (name "Net-(C18-Pad1)") (class "Default")
      (node (ref "C18") (pin "1") (pinfunction "1_1") (pintype "unspecified"))
      (node (ref "CAP13") (pin "1") (pinfunction "1_1") (pintype "unspecified"))
      (node (ref "CAP17") (pin "1") (pinfunction "1_1") (pintype "unspecified"))
      (node (ref "CN3") (pin "1") (pinfunction "1_1") (pintype "unspecified"))
      (node (ref "L4") (pin "2") (pinfunction "2_2") (pintype "unspecified"))
      (node (ref "POTANT3") (pin "1") (pinfunction "1_1") (pintype "input"))
      (node (ref "TVS4") (pin "1") (pinfunction "1_1") (pintype "unspecified"))
    )
    (net (code "10") (name "Net-(C19-Pad1)") (class "Default")
      (node (ref "C19") (pin "1") (pinfunction "1_1") (pintype "unspecified"))
      (node (ref "CAP14") (pin "1") (pinfunction "1_1") (pintype "unspecified"))
      (node (ref "CAP18") (pin "1") (pinfunction "1_1") (pintype "unspecified"))
      (node (ref "CN4") (pin "1") (pinfunction "1_1") (pintype "unspecified"))
      (node (ref "L5") (pin "2") (pinfunction "2_2") (pintype "unspecified"))
      (node (ref "POTANT4") (pin "1") (pinfunction "1_1") (pintype "input"))
      (node (ref "TVS5") (pin "1") (pinfunction "1_1") (pintype "unspecified"))
    )
    (net (code "11") (name "Net-(DC4-Pad2)") (class "Default")
      (node (ref "DC4") (pin "2") (pinfunction "2_2") (pintype "unspecified"))
      (node (ref "DR6") (pin "1") (pinfunction "1_1") (pintype "unspecified"))
    )
    (net (code "12") (name "Net-(DD1-C)") (class "Default")
      (node (ref "DC1") (pin "2") (pinfunction "2_2") (pintype "unspecified"))
      (node (ref "DD1") (pin "1") (pinfunction "C_1") (pintype "unspecified"))
      (node (ref "U0") (pin "11") (pinfunction "BOOT_11") (pintype "unspecified"))
    )
    (net (code "13") (name "Net-(L1-Pad1)") (class "Default")
      (node (ref "L1") (pin "1") (pinfunction "1_1") (pintype "unspecified"))
      (node (ref "R1") (pin "2") (pinfunction "2_2") (pintype "unspecified"))
      (node (ref "R2") (pin "2") (pinfunction "2_2") (pintype "unspecified"))
      (node (ref "R4") (pin "2") (pinfunction "2_2") (pintype "unspecified"))
    )
    (net (code "14") (name "Net-(M1-G)") (class "Default")
      (node (ref "DR7") (pin "2") (pinfunction "2_2") (pintype "unspecified"))
      (node (ref "M1") (pin "4") (pinfunction "G_4") (pintype "unspecified"))
    )
    (net (code "15") (name "Net-(M2-G)") (class "Default")
      (node (ref "M2") (pin "4") (pinfunction "G_4") (pintype "unspecified"))
      (node (ref "U0") (pin "13") (pinfunction "HDRV_13") (pintype "unspecified"))
    )
    (net (code "16") (name "Net-(TVS1-C)") (class "Default")
      (node (ref "F1") (pin "1") (pinfunction "1_1") (pintype "unspecified"))
      (node (ref "TVS1") (pin "1") (pinfunction "C_1") (pintype "unspecified"))
      (node (ref "U23") (pin "1") (pinfunction "1_1") (pintype "unspecified"))
      (node (ref "U23") (pin "4") (pinfunction "4_4") (pintype "unspecified"))
    )
    (net (code "17") (name "Net-(U0-COMP)") (class "Default")
      (node (ref "DC3") (pin "2") (pinfunction "2_2") (pintype "unspecified"))
      (node (ref "DR6") (pin "2") (pinfunction "2_2") (pintype "unspecified"))
      (node (ref "U0") (pin "3") (pinfunction "COMP_3") (pintype "unspecified"))
    )
    (net (code "18") (name "Net-(U0-EN)") (class "Default")
      (node (ref "DR2") (pin "1") (pinfunction "1_1") (pintype "unspecified"))
      (node (ref "DR3") (pin "2") (pinfunction "2_2") (pintype "unspecified"))
      (node (ref "U0") (pin "15") (pinfunction "EN_15") (pintype "unspecified"))
    )
    (net (code "19") (name "Net-(U0-LDRV)") (class "Default")
      (node (ref "DR7") (pin "1") (pinfunction "1_1") (pintype "unspecified"))
      (node (ref "U0") (pin "8") (pinfunction "LDRV_8") (pintype "unspecified"))
    )
    (net (code "20") (name "Net-(U0-PGOOD)") (class "Default")
      (node (ref "DR1") (pin "1") (pinfunction "1_1") (pintype "unspecified"))
      (node (ref "U0") (pin "14") (pinfunction "PGOOD_14") (pintype "unspecified"))
    )
    (net (code "21") (name "Net-(U0-RT{slash}CLK)") (class "Default")
      (node (ref "DR4") (pin "1") (pinfunction "1_1") (pintype "unspecified"))
      (node (ref "U0") (pin "1") (pinfunction "RT/CLK_1") (pintype "unspecified"))
    )
    (net (code "22") (name "Net-(U0-SS{slash}TR)") (class "Default")
      (node (ref "DC2") (pin "2") (pinfunction "2_2") (pintype "unspecified"))
      (node (ref "U0") (pin "2") (pinfunction "SS/TR_2") (pintype "unspecified"))
    )
    (net (code "23") (name "Net-(U0-SW)") (class "Default")
      (node (ref "DC1") (pin "1") (pinfunction "1_1") (pintype "unspecified"))
      (node (ref "L1") (pin "2") (pinfunction "2_2") (pintype "unspecified"))
      (node (ref "M1") (pin "5") (pinfunction "D_5") (pintype "unspecified"))
      (node (ref "M1") (pin "6") (pinfunction "D_6") (pintype "unspecified"))
      (node (ref "M1") (pin "7") (pinfunction "D_7") (pintype "unspecified"))
      (node (ref "M1") (pin "8") (pinfunction "D_8") (pintype "unspecified"))
      (node (ref "M1") (pin "9") (pinfunction "D_9") (pintype "unspecified"))
      (node (ref "M2") (pin "1") (pinfunction "S_1") (pintype "unspecified"))
      (node (ref "M2") (pin "2") (pinfunction "S_2") (pintype "unspecified"))
      (node (ref "M2") (pin "3") (pinfunction "S_3") (pintype "unspecified"))
      (node (ref "R5") (pin "2") (pinfunction "2_2") (pintype "unspecified"))
      (node (ref "U0") (pin "12") (pinfunction "SW_12") (pintype "unspecified"))
    )
    (net (code "24") (name "Net-(U0-VCC)") (class "Default")
      (node (ref "DR5") (pin "1") (pinfunction "1_1") (pintype "unspecified"))
      (node (ref "U0") (pin "10") (pinfunction "VCC_10") (pintype "unspecified"))
    )
    (net (code "25") (name "Net-(U1-FB)") (class "Default")
      (node (ref "POTANT1") (pin "2") (pinfunction "2_2") (pintype "input"))
      (node (ref "POTANT1") (pin "3") (pinfunction "3_3") (pintype "input"))
      (node (ref "R8") (pin "1") (pinfunction "1_1") (pintype "unspecified"))
      (node (ref "U1") (pin "2") (pinfunction "FB_2") (pintype "unspecified"))
    )
    (net (code "26") (name "Net-(U1-SW)") (class "Default")
      (node (ref "L2") (pin "1") (pinfunction "1_1") (pintype "unspecified"))
      (node (ref "S1") (pin "2") (pinfunction "2_2") (pintype "unspecified"))
      (node (ref "U1") (pin "3") (pinfunction "SW_3") (pintype "unspecified"))
    )
    (net (code "27") (name "Net-(U1-VC)") (class "Default")
      (node (ref "C12") (pin "1") (pinfunction "1_1") (pintype "unspecified"))
      (node (ref "U1") (pin "4") (pinfunction "VC_4") (pintype "unspecified"))
    )
    (net (code "28") (name "Net-(U1-VIN)") (class "Default")
      (node (ref "C12") (pin "2") (pinfunction "2_2") (pintype "unspecified"))
      (node (ref "C8") (pin "1") (pinfunction "1_1") (pintype "unspecified"))
      (node (ref "CAP3") (pin "1") (pinfunction "1_1") (pintype "unspecified"))
      (node (ref "CAP7") (pin "1") (pinfunction "1_1") (pintype "input"))
      (node (ref "F2") (pin "2") (pinfunction "2_2") (pintype "unspecified"))
      (node (ref "U1") (pin "5") (pinfunction "VIN_5") (pintype "unspecified"))
    )
    (net (code "29") (name "Net-(U2-FB)") (class "Default")
      (node (ref "POTANT2") (pin "2") (pinfunction "2_2") (pintype "input"))
      (node (ref "POTANT2") (pin "3") (pinfunction "3_3") (pintype "input"))
      (node (ref "R9") (pin "1") (pinfunction "1_1") (pintype "unspecified"))
      (node (ref "U2") (pin "2") (pinfunction "FB_2") (pintype "unspecified"))
    )
    (net (code "30") (name "Net-(U2-SW)") (class "Default")
      (node (ref "L3") (pin "1") (pinfunction "1_1") (pintype "unspecified"))
      (node (ref "S2") (pin "2") (pinfunction "2_2") (pintype "unspecified"))
      (node (ref "U2") (pin "3") (pinfunction "SW_3") (pintype "unspecified"))
    )
    (net (code "31") (name "Net-(U2-VC)") (class "Default")
      (node (ref "C13") (pin "1") (pinfunction "1_1") (pintype "unspecified"))
      (node (ref "U2") (pin "4") (pinfunction "VC_4") (pintype "unspecified"))
    )
    (net (code "32") (name "Net-(U2-VIN)") (class "Default")
      (node (ref "C13") (pin "2") (pinfunction "2_2") (pintype "unspecified"))
      (node (ref "C9") (pin "1") (pinfunction "1_1") (pintype "unspecified"))
      (node (ref "CAP4") (pin "1") (pinfunction "1_1") (pintype "unspecified"))
      (node (ref "CAP8") (pin "1") (pinfunction "1_1") (pintype "input"))
      (node (ref "F3") (pin "2") (pinfunction "2_2") (pintype "unspecified"))
      (node (ref "U2") (pin "5") (pinfunction "VIN_5") (pintype "unspecified"))
    )
    (net (code "33") (name "Net-(U3-FB)") (class "Default")
      (node (ref "POTANT3") (pin "2") (pinfunction "2_2") (pintype "input"))
      (node (ref "POTANT3") (pin "3") (pinfunction "3_3") (pintype "input"))
      (node (ref "R10") (pin "1") (pinfunction "1_1") (pintype "unspecified"))
      (node (ref "U3") (pin "2") (pinfunction "FB_2") (pintype "unspecified"))
    )
    (net (code "34") (name "Net-(U3-SW)") (class "Default")
      (node (ref "L4") (pin "1") (pinfunction "1_1") (pintype "unspecified"))
      (node (ref "S3") (pin "2") (pinfunction "2_2") (pintype "unspecified"))
      (node (ref "U3") (pin "3") (pinfunction "SW_3") (pintype "unspecified"))
    )
    (net (code "35") (name "Net-(U3-VC)") (class "Default")
      (node (ref "C14") (pin "1") (pinfunction "1_1") (pintype "unspecified"))
      (node (ref "U3") (pin "4") (pinfunction "VC_4") (pintype "unspecified"))
    )
    (net (code "36") (name "Net-(U3-VIN)") (class "Default")
      (node (ref "C10") (pin "1") (pinfunction "1_1") (pintype "unspecified"))
      (node (ref "C14") (pin "2") (pinfunction "2_2") (pintype "unspecified"))
      (node (ref "CAP5") (pin "1") (pinfunction "1_1") (pintype "unspecified"))
      (node (ref "CAP9") (pin "1") (pinfunction "1_1") (pintype "input"))
      (node (ref "F4") (pin "2") (pinfunction "2_2") (pintype "unspecified"))
      (node (ref "U3") (pin "5") (pinfunction "VIN_5") (pintype "unspecified"))
    )
    (net (code "37") (name "Net-(U4-FB)") (class "Default")
      (node (ref "POTANT4") (pin "2") (pinfunction "2_2") (pintype "input"))
      (node (ref "POTANT4") (pin "3") (pinfunction "3_3") (pintype "input"))
      (node (ref "R11") (pin "1") (pinfunction "1_1") (pintype "unspecified"))
      (node (ref "U4") (pin "2") (pinfunction "FB_2") (pintype "unspecified"))
    )
    (net (code "38") (name "Net-(U4-SW)") (class "Default")
      (node (ref "L5") (pin "1") (pinfunction "1_1") (pintype "unspecified"))
      (node (ref "S4") (pin "2") (pinfunction "2_2") (pintype "unspecified"))
      (node (ref "U4") (pin "3") (pinfunction "SW_3") (pintype "unspecified"))
    )
    (net (code "39") (name "Net-(U4-VC)") (class "Default")
      (node (ref "C15") (pin "2") (pinfunction "2_2") (pintype "unspecified"))
      (node (ref "U4") (pin "4") (pinfunction "VC_4") (pintype "unspecified"))
    )
    (net (code "40") (name "Net-(U4-VIN)") (class "Default")
      (node (ref "C11") (pin "1") (pinfunction "1_1") (pintype "unspecified"))
      (node (ref "C15") (pin "1") (pinfunction "1_1") (pintype "unspecified"))
      (node (ref "CAP10") (pin "1") (pinfunction "1_1") (pintype "input"))
      (node (ref "CAP6") (pin "1") (pinfunction "1_1") (pintype "unspecified"))
      (node (ref "F5") (pin "2") (pinfunction "2_2") (pintype "unspecified"))
      (node (ref "U4") (pin "5") (pinfunction "VIN_5") (pintype "unspecified"))
    )
    (net (code "41") (name "VCC") (class "Default")
      (node (ref "DD1") (pin "2") (pinfunction "A_2") (pintype "unspecified"))
      (node (ref "DR1") (pin "2") (pinfunction "2_2") (pintype "unspecified"))
      (node (ref "DR5") (pin "2") (pinfunction "2_2") (pintype "unspecified"))
    )
    (net (code "42") (name "VIN") (class "Default")
      (node (ref "DC6") (pin "2") (pinfunction "2_2") (pintype "unspecified"))
      (node (ref "DR2") (pin "2") (pinfunction "2_2") (pintype "unspecified"))
      (node (ref "U0") (pin "7") (pinfunction "VIN_7") (pintype "unspecified"))
    )
  )
)
